# breakout.net
KiCad netlist of a schematic drawn in EAGLE
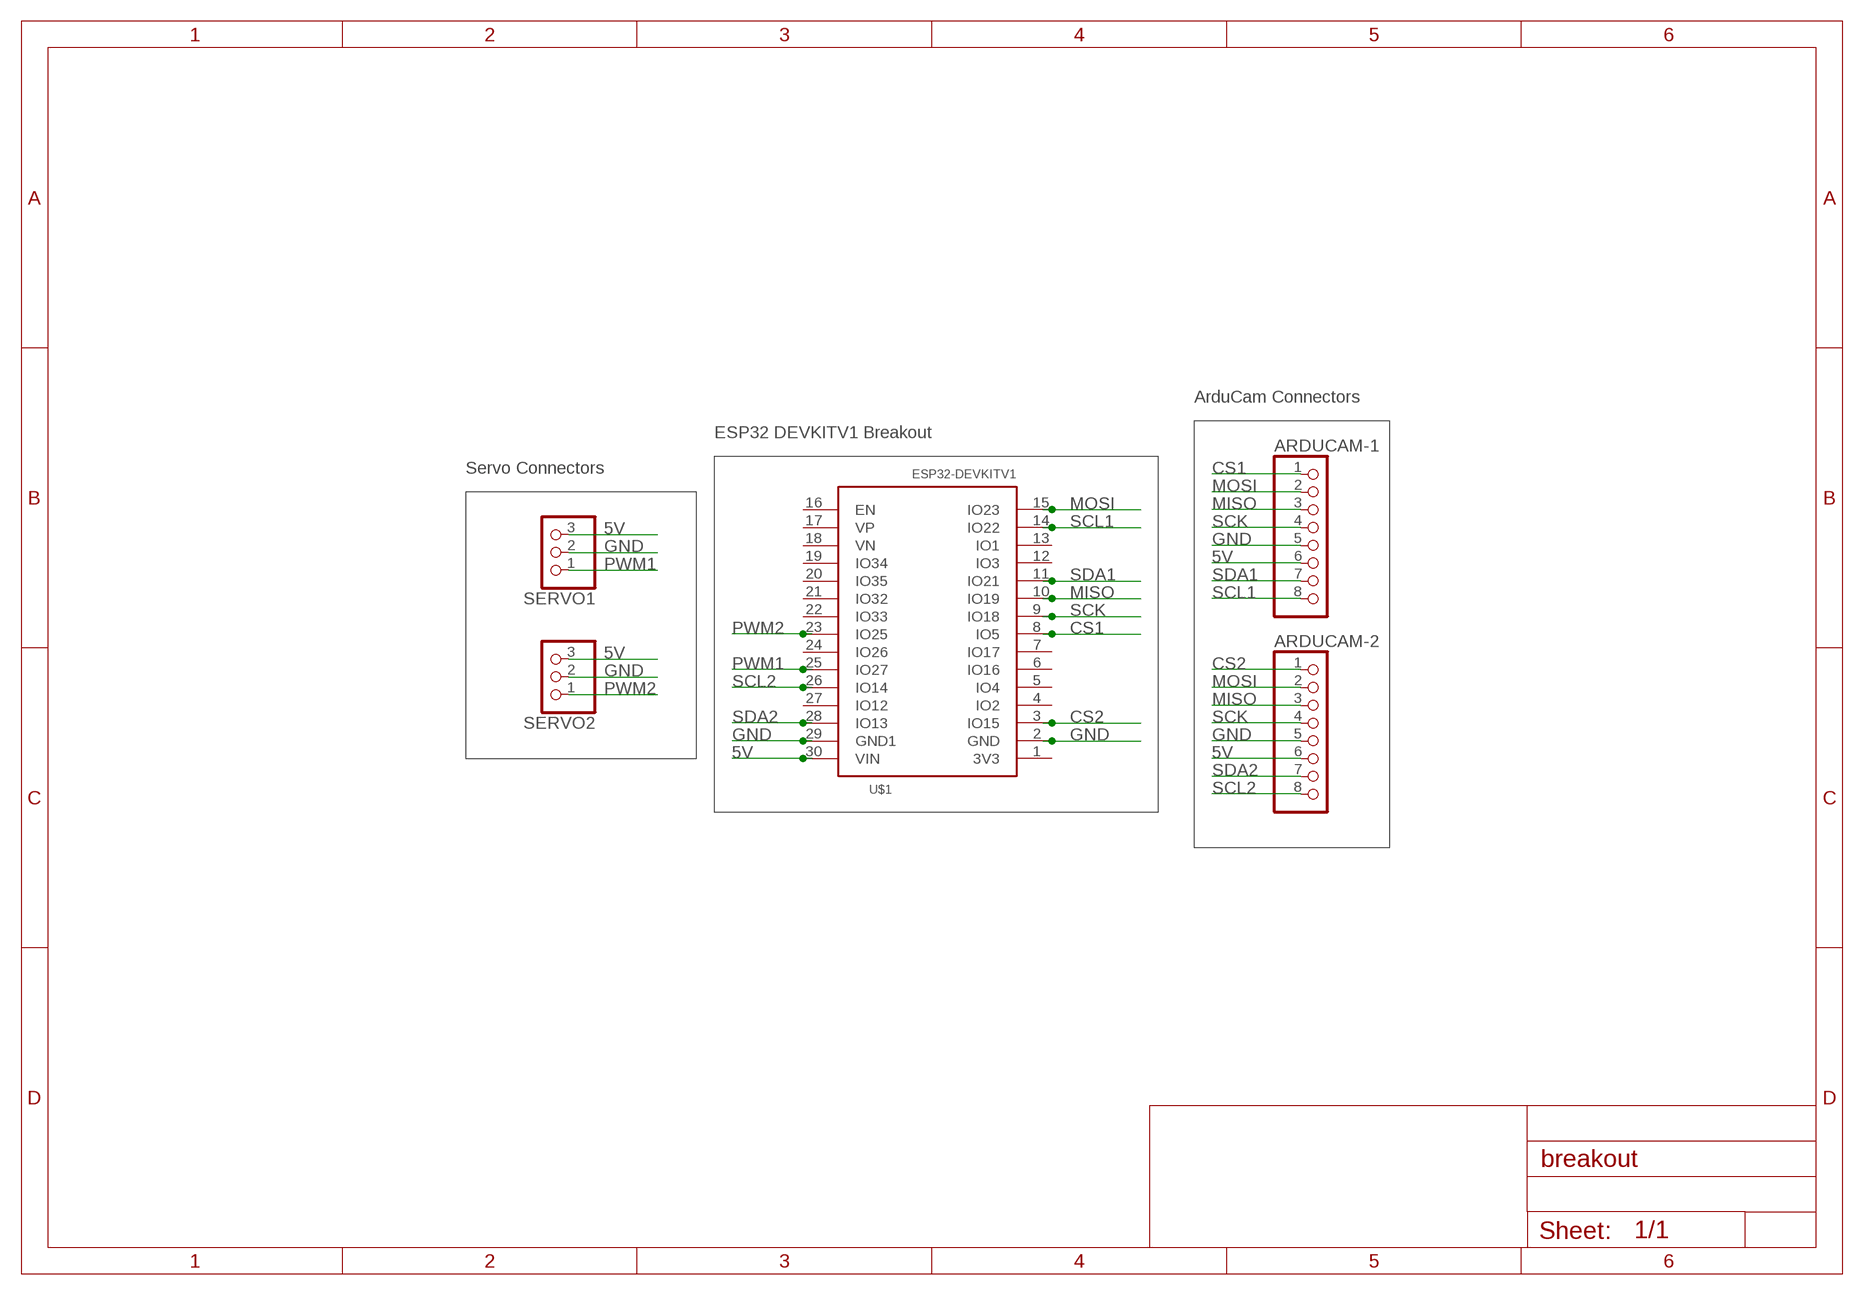
[diagram p0: schematic, sheet 1]

(export (version "E")
  (design (tool "Eeschema 10.0.6"))
  (components
    (comp (ref "ARDUCAM-1")
      (value "PINHD-1X8BIG")
      (footprint "eagle-import:1X08-BIG")
      (libsource (lib "eagle-import") (part "PINHD-1X8BIG"))
    )
    (comp (ref "ARDUCAM-2")
      (value "PINHD-1X8BIG")
      (footprint "eagle-import:1X08-BIG")
      (libsource (lib "eagle-import") (part "PINHD-1X8BIG"))
    )
    (comp (ref "SERVO1")
      (value "PINHD-1X3")
      (footprint "eagle-import:1X03")
      (libsource (lib "eagle-import") (part "PINHD-1X3"))
    )
    (comp (ref "SERVO2")
      (value "PINHD-1X3")
      (footprint "eagle-import:1X03")
      (libsource (lib "eagle-import") (part "PINHD-1X3"))
    )
    (comp (ref "U$1")
      (value "ESP32DEVKITV1")
      (footprint "eagle-import:ESP32-DEVKITV1")
      (libsource (lib "eagle-import") (part "ESP32DEVKITV1"))
    )
  )
  (nets
    (net (code "1") (name "/5V") (class "Default")
      (node (ref "ARDUCAM-1") (pin "6") (pinfunction "6_6") (pintype "passive"))
      (node (ref "ARDUCAM-2") (pin "6") (pinfunction "6_6") (pintype "passive"))
      (node (ref "SERVO1") (pin "3") (pinfunction "3_3") (pintype "passive"))
      (node (ref "SERVO2") (pin "3") (pinfunction "3_3") (pintype "passive"))
      (node (ref "U$1") (pin "30") (pinfunction "VIN_30") (pintype "bidirectional"))
    )
    (net (code "2") (name "/CS1") (class "Default")
      (node (ref "ARDUCAM-1") (pin "1") (pinfunction "1_1") (pintype "passive"))
      (node (ref "U$1") (pin "8") (pinfunction "IO5_8") (pintype "bidirectional"))
    )
    (net (code "3") (name "/CS2") (class "Default")
      (node (ref "ARDUCAM-2") (pin "1") (pinfunction "1_1") (pintype "passive"))
      (node (ref "U$1") (pin "3") (pinfunction "IO15_3") (pintype "bidirectional"))
    )
    (net (code "4") (name "/GND") (class "Default")
      (node (ref "ARDUCAM-1") (pin "5") (pinfunction "5_5") (pintype "passive"))
      (node (ref "ARDUCAM-2") (pin "5") (pinfunction "5_5") (pintype "passive"))
      (node (ref "SERVO1") (pin "2") (pinfunction "2_2") (pintype "passive"))
      (node (ref "SERVO2") (pin "2") (pinfunction "2_2") (pintype "passive"))
      (node (ref "U$1") (pin "2") (pinfunction "GND_2") (pintype "bidirectional"))
      (node (ref "U$1") (pin "29") (pinfunction "GND1_29") (pintype "bidirectional"))
    )
    (net (code "5") (name "/MISO") (class "Default")
      (node (ref "ARDUCAM-1") (pin "3") (pinfunction "3_3") (pintype "passive"))
      (node (ref "ARDUCAM-2") (pin "3") (pinfunction "3_3") (pintype "passive"))
      (node (ref "U$1") (pin "10") (pinfunction "IO19_10") (pintype "bidirectional"))
    )
    (net (code "6") (name "/MOSI") (class "Default")
      (node (ref "ARDUCAM-1") (pin "2") (pinfunction "2_2") (pintype "passive"))
      (node (ref "ARDUCAM-2") (pin "2") (pinfunction "2_2") (pintype "passive"))
      (node (ref "U$1") (pin "15") (pinfunction "IO23_15") (pintype "bidirectional"))
    )
    (net (code "7") (name "/PWM1") (class "Default")
      (node (ref "SERVO1") (pin "1") (pinfunction "1_1") (pintype "passive"))
      (node (ref "U$1") (pin "25") (pinfunction "IO27_25") (pintype "bidirectional"))
    )
    (net (code "8") (name "/PWM2") (class "Default")
      (node (ref "SERVO2") (pin "1") (pinfunction "1_1") (pintype "passive"))
      (node (ref "U$1") (pin "23") (pinfunction "IO25_23") (pintype "bidirectional"))
    )
    (net (code "9") (name "/SCK") (class "Default")
      (node (ref "ARDUCAM-1") (pin "4") (pinfunction "4_4") (pintype "passive"))
      (node (ref "ARDUCAM-2") (pin "4") (pinfunction "4_4") (pintype "passive"))
      (node (ref "U$1") (pin "9") (pinfunction "IO18_9") (pintype "bidirectional"))
    )
    (net (code "10") (name "/SCL1") (class "Default")
      (node (ref "ARDUCAM-1") (pin "8") (pinfunction "8_8") (pintype "passive"))
      (node (ref "U$1") (pin "14") (pinfunction "IO22_14") (pintype "bidirectional"))
    )
    (net (code "11") (name "/SCL2") (class "Default")
      (node (ref "ARDUCAM-2") (pin "8") (pinfunction "8_8") (pintype "passive"))
      (node (ref "U$1") (pin "26") (pinfunction "IO14_26") (pintype "bidirectional"))
    )
    (net (code "12") (name "/SDA1") (class "Default")
      (node (ref "ARDUCAM-1") (pin "7") (pinfunction "7_7") (pintype "passive"))
      (node (ref "U$1") (pin "11") (pinfunction "IO21_11") (pintype "bidirectional"))
    )
    (net (code "13") (name "/SDA2") (class "Default")
      (node (ref "ARDUCAM-2") (pin "7") (pinfunction "7_7") (pintype "passive"))
      (node (ref "U$1") (pin "28") (pinfunction "IO13_28") (pintype "bidirectional"))
    )
    (net (code "14") (name "unconnected-(U$1-3V3-Pad1)") (class "Default")
      (node (ref "U$1") (pin "1") (pinfunction "3V3_1") (pintype "bidirectional"))
    )
    (net (code "15") (name "unconnected-(U$1-EN-Pad16)") (class "Default")
      (node (ref "U$1") (pin "16") (pinfunction "EN_16") (pintype "bidirectional"))
    )
    (net (code "16") (name "unconnected-(U$1-IO1-Pad13)") (class "Default")
      (node (ref "U$1") (pin "13") (pinfunction "IO1_13") (pintype "bidirectional"))
    )
    (net (code "17") (name "unconnected-(U$1-IO2-Pad4)") (class "Default")
      (node (ref "U$1") (pin "4") (pinfunction "IO2_4") (pintype "bidirectional"))
    )
    (net (code "18") (name "unconnected-(U$1-IO3-Pad12)") (class "Default")
      (node (ref "U$1") (pin "12") (pinfunction "IO3_12") (pintype "bidirectional"))
    )
    (net (code "19") (name "unconnected-(U$1-IO4-Pad5)") (class "Default")
      (node (ref "U$1") (pin "5") (pinfunction "IO4_5") (pintype "bidirectional"))
    )
    (net (code "20") (name "unconnected-(U$1-IO12-Pad27)") (class "Default")
      (node (ref "U$1") (pin "27") (pinfunction "IO12_27") (pintype "bidirectional"))
    )
    (net (code "21") (name "unconnected-(U$1-IO16-Pad6)") (class "Default")
      (node (ref "U$1") (pin "6") (pinfunction "IO16_6") (pintype "bidirectional"))
    )
    (net (code "22") (name "unconnected-(U$1-IO17-Pad7)") (class "Default")
      (node (ref "U$1") (pin "7") (pinfunction "IO17_7") (pintype "bidirectional"))
    )
    (net (code "23") (name "unconnected-(U$1-IO26-Pad24)") (class "Default")
      (node (ref "U$1") (pin "24") (pinfunction "IO26_24") (pintype "bidirectional"))
    )
    (net (code "24") (name "unconnected-(U$1-IO32-Pad21)") (class "Default")
      (node (ref "U$1") (pin "21") (pinfunction "IO32_21") (pintype "bidirectional"))
    )
    (net (code "25") (name "unconnected-(U$1-IO33-Pad22)") (class "Default")
      (node (ref "U$1") (pin "22") (pinfunction "IO33_22") (pintype "bidirectional"))
    )
    (net (code "26") (name "unconnected-(U$1-IO34-Pad19)") (class "Default")
      (node (ref "U$1") (pin "19") (pinfunction "IO34_19") (pintype "bidirectional"))
    )
    (net (code "27") (name "unconnected-(U$1-IO35-Pad20)") (class "Default")
      (node (ref "U$1") (pin "20") (pinfunction "IO35_20") (pintype "bidirectional"))
    )
    (net (code "28") (name "unconnected-(U$1-VN-Pad18)") (class "Default")
      (node (ref "U$1") (pin "18") (pinfunction "VN_18") (pintype "bidirectional"))
    )
    (net (code "29") (name "unconnected-(U$1-VP-Pad17)") (class "Default")
      (node (ref "U$1") (pin "17") (pinfunction "VP_17") (pintype "bidirectional"))
    )
  )
)
